# mcu_v1.net
KiCad netlist of a schematic drawn in Altium Designer
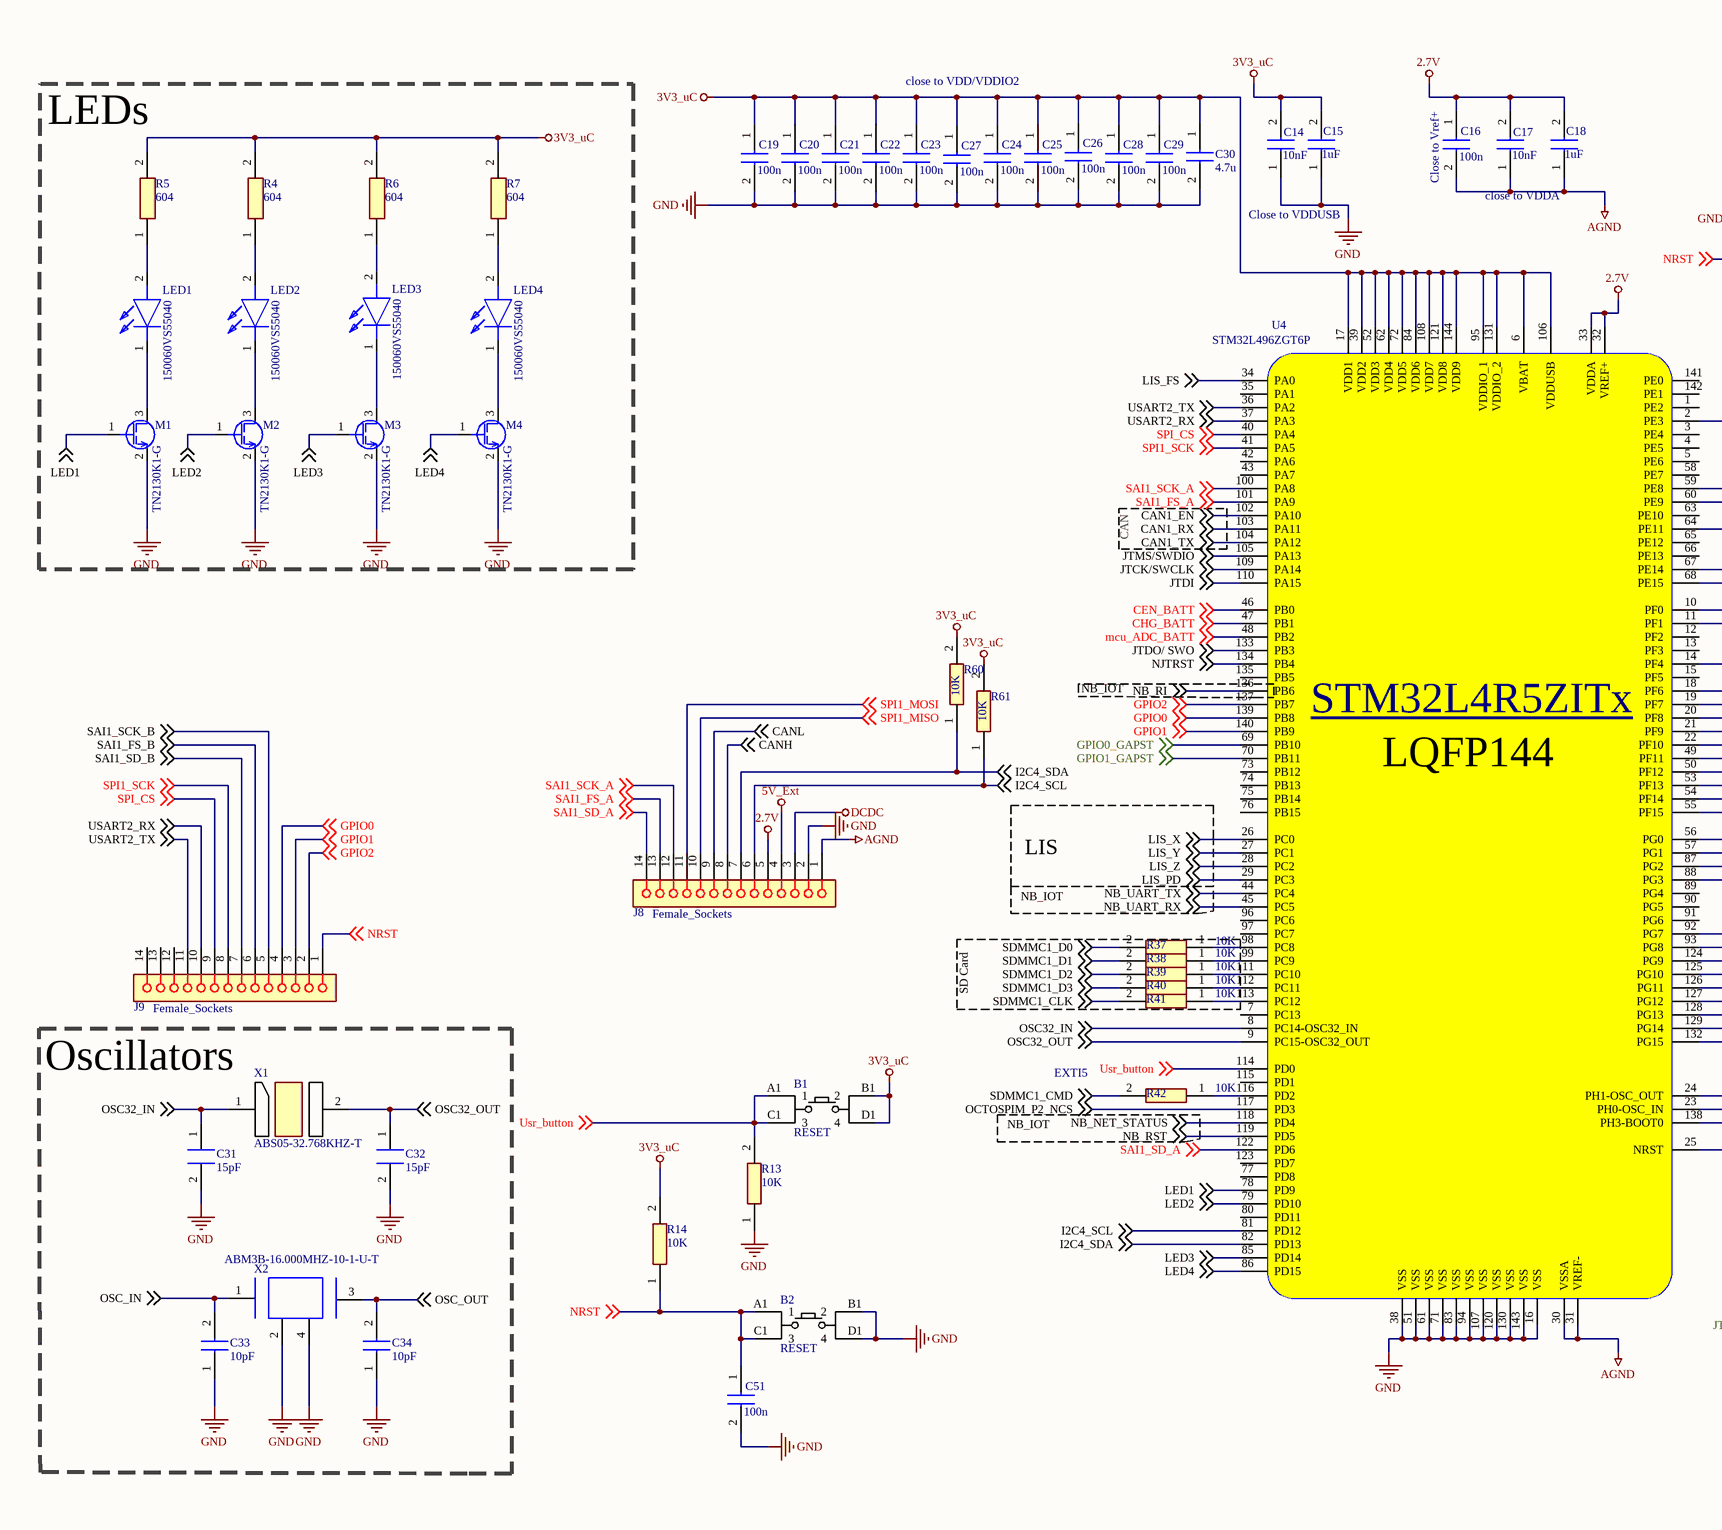
[diagram p0: mcu_v1.SchDoc, left]
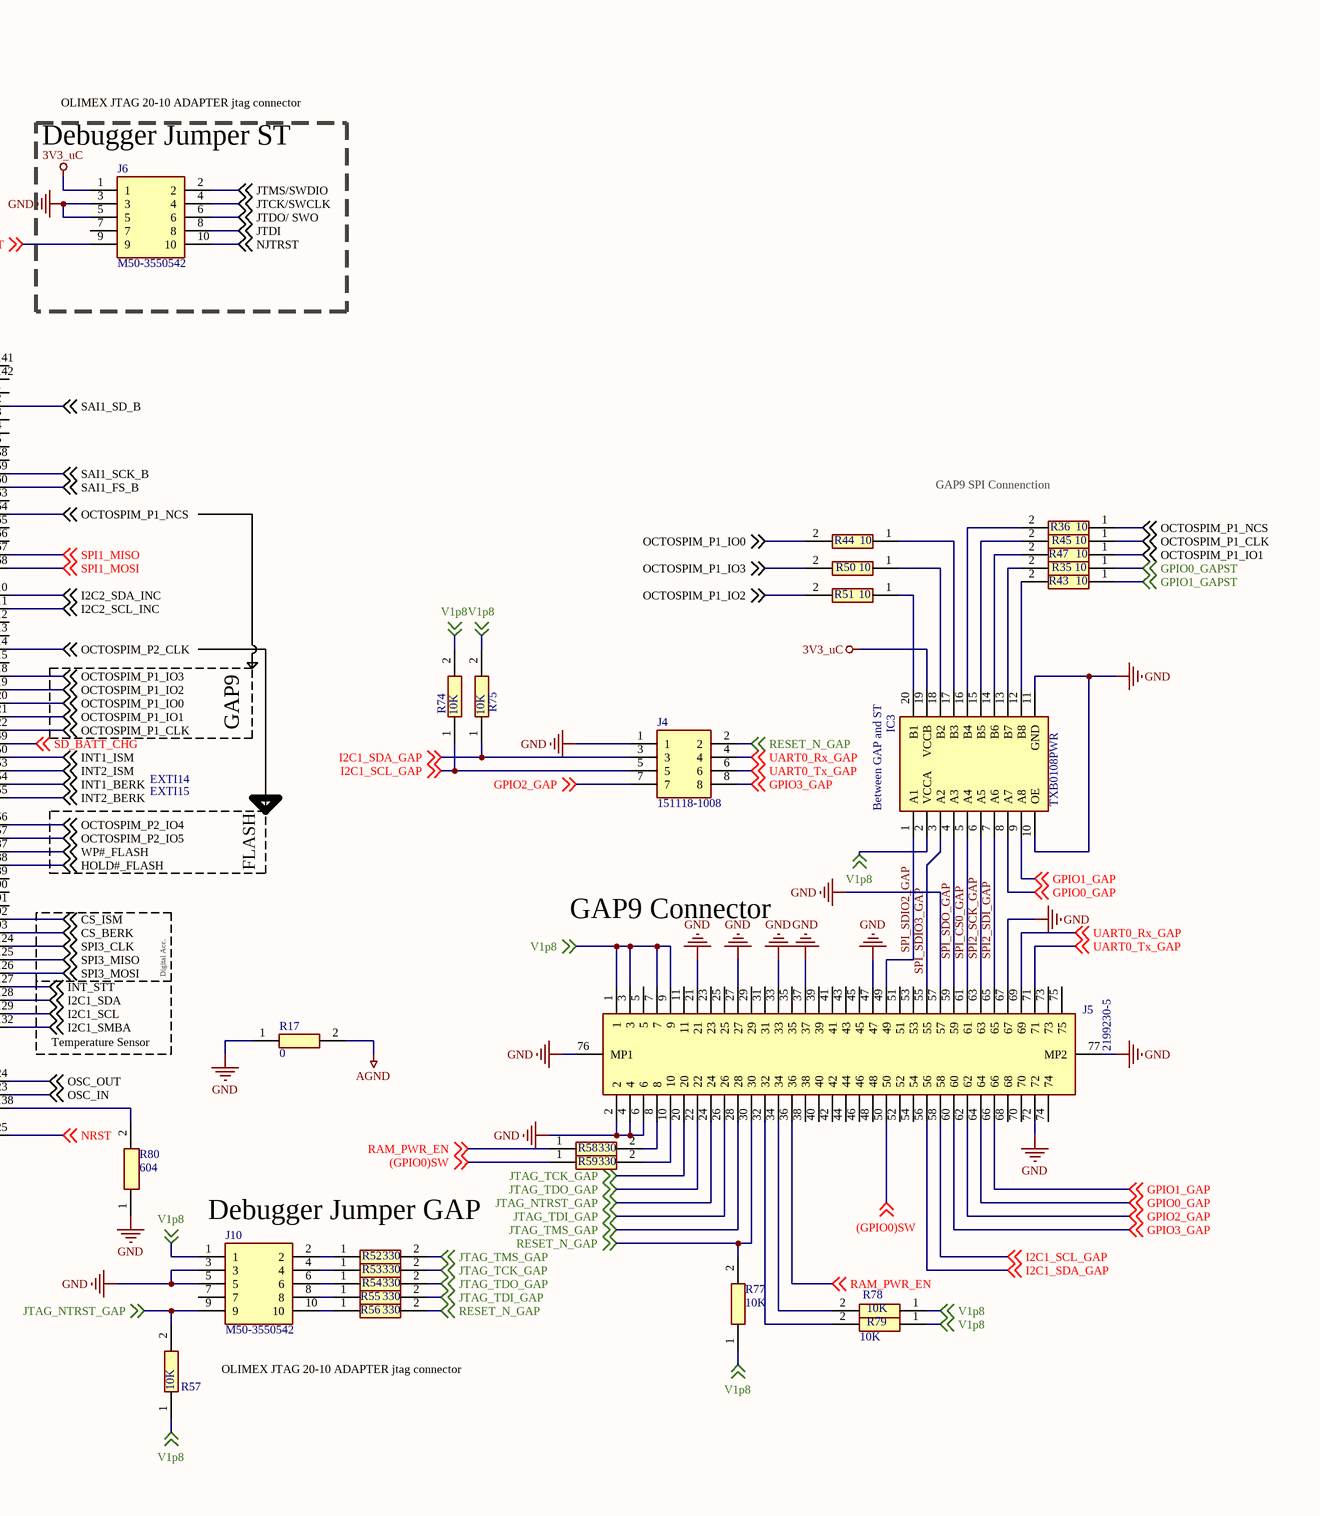
[diagram p1: mcu_v1.SchDoc, right]

(export (version "E")
  (design (tool "Eeschema 10.0.6"))
  (components
    (comp (ref "B1")
      (value "RESET")
      (footprint "PTS645SM43JSMTR92LFS")
      (description "Switch Tactile SPST N.O Round Button 12V 50mA 1.57N Solder Surface Mount T/R")
      (fields
        (field (name "MANUFACTURER") "C&K Components")
        (field (name "MANUFACTURER PART NUMBER") "PTS645SM43JSMTR92LFS")
      )
      (libsource (lib "shm_schem_lib") (part "PTS645SM43JSMTR92LFS"))
    )
    (comp (ref "B2")
      (value "RESET")
      (footprint "PTS645SM43JSMTR92LFS")
      (description "Switch Tactile SPST N.O Round Button 12V 50mA 1.57N Solder Surface Mount T/R")
      (fields
        (field (name "MANUFACTURER") "C&K Components")
        (field (name "MANUFACTURER PART NUMBER") "PTS645SM43JSMTR92LFS")
      )
      (libsource (lib "shm_schem_lib") (part "PTS645SM43JSMTR92LFS"))
    )
    (comp (ref "C14")
      (value "10nF")
      (footprint "SamacSys:CAPC1608X87N")
      (description "Capacitor")
      (fields (field (name "MANUFACTURER_PART_NUMBER") "885012206014"))
      (libsource (lib "*") (part "885012206014"))
    )
    (comp (ref "C15")
      (value "1uF")
      (footprint "SamacSys:CAPC2012X100N")
      (description "Capacitor")
      (fields (field (name "MANUFACTURER_PART_NUMBER") "C0805C105K4RACTU"))
      (libsource (lib "*") (part "C0805C105K4RACTU"))
    )
    (comp (ref "C16")
      (value "100n")
      (footprint "SamacSys:CAPC1608X87N")
      (description "Capacitor")
      (fields (field (name "MANUFACTURER_PART_NUMBER") "885012206071"))
      (libsource (lib "*") (part "885012206071"))
    )
    (comp (ref "C17")
      (value "10nF")
      (footprint "CAPC1608X87N")
      (description "Capacitor")
      (fields (field (name "MANUFACTURER_PART_NUMBER") "885012206014"))
      (libsource (lib "*") (part "885012206014"))
    )
    (comp (ref "C18")
      (value "1uF")
      (footprint "SamacSys:CAPC2012X100N")
      (description "Capacitor")
      (fields (field (name "MANUFACTURER_PART_NUMBER") "C0805C105K4RACTU"))
      (libsource (lib "*") (part "C0805C105K4RACTU"))
    )
    (comp (ref "C19")
      (value "100n")
      (footprint "SamacSys:CAPC1608X87N")
      (description "Capacitor")
      (fields (field (name "MANUFACTURER_PART_NUMBER") "885012206071"))
      (libsource (lib "*") (part "885012206071"))
    )
    (comp (ref "C20")
      (value "100n")
      (footprint "SamacSys:CAPC1608X87N")
      (description "Capacitor")
      (fields (field (name "MANUFACTURER_PART_NUMBER") "885012206071"))
      (libsource (lib "*") (part "885012206071"))
    )
    (comp (ref "C21")
      (value "100n")
      (footprint "SamacSys:CAPC1608X87N")
      (description "Capacitor")
      (fields (field (name "MANUFACTURER_PART_NUMBER") "885012206071"))
      (libsource (lib "*") (part "885012206071"))
    )
    (comp (ref "C22")
      (value "100n")
      (footprint "SamacSys:CAPC1608X87N")
      (description "Capacitor")
      (fields (field (name "MANUFACTURER_PART_NUMBER") "885012206071"))
      (libsource (lib "*") (part "885012206071"))
    )
    (comp (ref "C23")
      (value "100n")
      (footprint "SamacSys:CAPC1608X87N")
      (description "Capacitor")
      (fields (field (name "MANUFACTURER_PART_NUMBER") "885012206071"))
      (libsource (lib "*") (part "885012206071"))
    )
    (comp (ref "C24")
      (value "100n")
      (footprint "SamacSys:CAPC1608X87N")
      (description "Capacitor")
      (fields (field (name "MANUFACTURER_PART_NUMBER") "885012206071"))
      (libsource (lib "*") (part "885012206071"))
    )
    (comp (ref "C25")
      (value "100n")
      (footprint "SamacSys:CAPC1608X87N")
      (description "Capacitor")
      (fields (field (name "MANUFACTURER_PART_NUMBER") "885012206071"))
      (libsource (lib "*") (part "885012206071"))
    )
    (comp (ref "C26")
      (value "100n")
      (footprint "SamacSys:CAPC1608X87N")
      (description "Capacitor")
      (fields (field (name "MANUFACTURER_PART_NUMBER") "885012206071"))
      (libsource (lib "*") (part "885012206071"))
    )
    (comp (ref "C27")
      (value "100n")
      (footprint "SamacSys:CAPC1608X87N")
      (description "Capacitor")
      (fields (field (name "MANUFACTURER_PART_NUMBER") "885012206071"))
      (libsource (lib "*") (part "885012206071"))
    )
    (comp (ref "C28")
      (value "100n")
      (footprint "SamacSys:CAPC1608X87N")
      (description "Capacitor")
      (fields (field (name "MANUFACTURER_PART_NUMBER") "885012206071"))
      (libsource (lib "*") (part "885012206071"))
    )
    (comp (ref "C29")
      (value "100n")
      (footprint "SamacSys:CAPC1608X87N")
      (description "Capacitor")
      (fields (field (name "MANUFACTURER_PART_NUMBER") "885012206071"))
      (libsource (lib "*") (part "885012206071"))
    )
    (comp (ref "C30")
      (value "4.7u")
      (footprint "SamacSys:CAPC3216X100N")
      (description "Capacitor")
      (fields (field (name "MANUFACTURER_PART_NUMBER") "C1206C224J1RACAUTO"))
      (libsource (lib "*") (part "C1206C224J1RACAUTO"))
    )
    (comp (ref "C31")
      (value "15pF")
      (footprint "CAPC1608X87N")
      (description "CAP CER 15PF 16V C0G/NP0 0603")
      (fields
        (field (name "MANUFACTURER") "Vishay Vitramon")
        (field (name "MANUFACTURER PART NUMBER") "VJ0603A150KXJPW1BC")
      )
      (libsource (lib "shm_schem_lib") (part "VJ0603A150KXJPW1BC"))
    )
    (comp (ref "C32")
      (value "15pF")
      (footprint "CAPC1608X87N")
      (description "CAP CER 15PF 16V C0G/NP0 0603")
      (fields
        (field (name "MANUFACTURER") "Vishay Vitramon")
        (field (name "MANUFACTURER PART NUMBER") "VJ0603A150KXJPW1BC")
      )
      (libsource (lib "shm_schem_lib") (part "VJ0603A150KXJPW1BC"))
    )
    (comp (ref "C33")
      (value "10pF")
      (footprint "SamacSys:CAPC1608X87N")
      (description "Capacitor")
      (fields
        (field (name "MOUSER2 PART NUMBER") "80-C0603C100K4GACTU")
        (field (name "MANUFACTURER_PART_NUMBER") "C0603C100K4GACTU")
      )
      (libsource (lib "*") (part "C0603C100K4GACTU"))
    )
    (comp (ref "C34")
      (value "10pF")
      (footprint "SamacSys:CAPC1608X87N")
      (description "Capacitor")
      (fields
        (field (name "MOUSER2 PART NUMBER") "80-C0603C100K4GACTU")
        (field (name "MANUFACTURER_PART_NUMBER") "C0603C100K4GACTU")
      )
      (libsource (lib "*") (part "C0603C100K4GACTU"))
    )
    (comp (ref "C51")
      (value "100n")
      (footprint "SamacSys:CAPC1608X87N")
      (description "Capacitor")
      (fields (field (name "MANUFACTURER_PART_NUMBER") "885012206071"))
      (libsource (lib "*") (part "885012206071"))
    )
    (comp (ref "IC3")
      (value "TXB0108PWR")
      (footprint "SOP65P640X120-20N")
      (description "Integrated Circuit")
      (fields (field (name "MOUSER2 PART NUMBER") "595-TXB0108PWR"))
      (libsource (lib "*") (part "TXB0108PWR"))
    )
    (comp (ref "J4")
      (value "151118-1008")
      (footprint "1511181008")
      (description "Connector")
      (libsource (lib "*") (part "151118-1008"))
    )
    (comp (ref "J5")
      (value "2199230-5")
      (footprint "21992305")
      (description "Connector")
      (fields (field (name "MOUSER2 PART NUMBER") "571-2199230-5"))
      (libsource (lib "*") (part "2199230-5"))
    )
    (comp (ref "J6")
      (value "M50-3550542")
      (footprint "SamacSys:SHDR10W40P127_2X5_2083X565X1160P")
      (description "Connector")
      (libsource (lib "*") (part "M50-3550542"))
    )
    (comp (ref "J8")
      (value "Female_Sockets")
      (footprint "BCS-114-XXX-S-TE")
      (description "Conn Socket Strip SKT 14 POS 2.54mm Solder ST Top Entry Thru-Hole TIGER CLAW™ Tube")
      (fields
        (field (name "MANUFACTURER") "Samtec")
        (field (name "MANUFACTURER PART NUMBER") "BCS-114-L-S-TE")
      )
      (libsource (lib "shm_schem_lib") (part "BCS-114-L-S-TE"))
    )
    (comp (ref "J9")
      (value "Female_Sockets")
      (footprint "BCS-114-XXX-S-TE")
      (description "Conn Socket Strip SKT 14 POS 2.54mm Solder ST Top Entry Thru-Hole TIGER CLAW™ Tube")
      (fields
        (field (name "MANUFACTURER") "Samtec")
        (field (name "MANUFACTURER PART NUMBER") "BCS-114-L-S-TE")
      )
      (libsource (lib "shm_schem_lib") (part "BCS-114-L-S-TE"))
    )
    (comp (ref "J10")
      (value "M50-3550542")
      (footprint "SHDR10W40P127_2X5_2083X565X1160P")
      (description "Connector")
      (libsource (lib "*") (part "M50-3550542"))
    )
    (comp (ref "LED1")
      (value "150060VS55040")
      (footprint "SamacSys:LEDM168X50N")
      (description "LED")
      (libsource (lib "*") (part "150060VS55040"))
    )
    (comp (ref "LED2")
      (value "150060VS55040")
      (footprint "SamacSys:LEDM168X50N")
      (description "LED")
      (libsource (lib "*") (part "150060VS55040"))
    )
    (comp (ref "LED3")
      (value "150060VS55040")
      (footprint "SamacSys:LEDM168X50N")
      (description "LED")
      (libsource (lib "*") (part "150060VS55040"))
    )
    (comp (ref "LED4")
      (value "150060VS55040")
      (footprint "SamacSys:LEDM168X50N")
      (description "LED")
      (libsource (lib "*") (part "150060VS55040"))
    )
    (comp (ref "M1")
      (value "TN2130K1-G")
      (footprint "SOT95P237X112-3N")
      (description "Mosfet, N-Channel Enhancement-Mode, 300V, 25 Ohm Rohs Compliant: Yes")
      (fields (field (name "MANUFACTURER") "Microchip Supertex"))
      (libsource (lib "shm_schem_lib") (part "TN2130K1-G"))
    )
    (comp (ref "M2")
      (value "TN2130K1-G")
      (footprint "SOT95P237X112-3N")
      (description "Mosfet, N-Channel Enhancement-Mode, 300V, 25 Ohm Rohs Compliant: Yes")
      (fields (field (name "MANUFACTURER") "Microchip Supertex"))
      (libsource (lib "shm_schem_lib") (part "TN2130K1-G"))
    )
    (comp (ref "M3")
      (value "TN2130K1-G")
      (footprint "SOT95P237X112-3N")
      (description "Mosfet, N-Channel Enhancement-Mode, 300V, 25 Ohm Rohs Compliant: Yes")
      (fields (field (name "MANUFACTURER") "Microchip Supertex"))
      (libsource (lib "shm_schem_lib") (part "TN2130K1-G"))
    )
    (comp (ref "M4")
      (value "TN2130K1-G")
      (footprint "SOT95P237X112-3N")
      (description "Mosfet, N-Channel Enhancement-Mode, 300V, 25 Ohm Rohs Compliant: Yes")
      (fields (field (name "MANUFACTURER") "Microchip Supertex"))
      (libsource (lib "shm_schem_lib") (part "TN2130K1-G"))
    )
    (comp (ref "R4")
      (value "604")
      (footprint "RESC1608X55N")
      (description "Res Thin Film 0603 604 Ohm 1% 1/10W ±50ppm/°C Molded SMD SMD Paper T/R")
      (fields
        (field (name "MANUFACTURER") "Yageo")
        (field (name "MANUFACTURER PART NUMBER") "RT0603FRE07604RL")
      )
      (libsource (lib "shm_schem_lib") (part "RT0603FRE07604RL"))
    )
    (comp (ref "R5")
      (value "604")
      (footprint "RESC1608X55N")
      (description "Res Thin Film 0603 604 Ohm 1% 1/10W ±50ppm/°C Molded SMD SMD Paper T/R")
      (fields
        (field (name "MANUFACTURER") "Yageo")
        (field (name "MANUFACTURER PART NUMBER") "RT0603FRE07604RL")
      )
      (libsource (lib "shm_schem_lib") (part "RT0603FRE07604RL"))
    )
    (comp (ref "R6")
      (value "604")
      (footprint "RESC1608X55N")
      (description "Res Thin Film 0603 604 Ohm 1% 1/10W ±50ppm/°C Molded SMD SMD Paper T/R")
      (fields
        (field (name "MANUFACTURER") "Yageo")
        (field (name "MANUFACTURER PART NUMBER") "RT0603FRE07604RL")
      )
      (libsource (lib "shm_schem_lib") (part "RT0603FRE07604RL"))
    )
    (comp (ref "R7")
      (value "604")
      (footprint "RESC1608X55N")
      (description "Res Thin Film 0603 604 Ohm 1% 1/10W ±50ppm/°C Molded SMD SMD Paper T/R")
      (fields
        (field (name "MANUFACTURER") "Yageo")
        (field (name "MANUFACTURER PART NUMBER") "RT0603FRE07604RL")
      )
      (libsource (lib "shm_schem_lib") (part "RT0603FRE07604RL"))
    )
    (comp (ref "R13")
      (value "10K")
      (footprint "ERJ3EK_(0603)")
      (description "Resistor")
      (fields
        (field (name "MOUSER2 PART NUMBER") "667-ERJ-3EKF1002V")
        (field (name "MANUFACTURER_PART_NUMBER") "ERJ-3EKF1002V")
      )
      (libsource (lib "*") (part "ERJ-3EKF1002V"))
    )
    (comp (ref "R14")
      (value "10K")
      (footprint "RESC1608X55N")
      (description "Resistor")
      (fields
        (field (name "MOUSER2 PART NUMBER") "667-ERJ-3EKF1002V")
        (field (name "MANUFACTURER_PART_NUMBER") "ERJ-3EKF1002V")
      )
      (libsource (lib "*") (part "ERJ-3EKF1002V"))
    )
    (comp (ref "R17")
      (value "0")
      (footprint "SamacSys:RESC1608X55N")
      (description "Resistor")
      (fields (field (name "MANUFACTURER_PART_NUMBER") "RC0603FR-070RL"))
      (libsource (lib "*") (part "RC0603FR-070RL"))
    )
    (comp (ref "R35")
      (value "10")
      (footprint "SamacSys:RESC1005X40N")
      (description "Resistor")
      (fields (field (name "MANUFACTURER_PART_NUMBER") "CR0402-FX-10R0GLF"))
      (libsource (lib "*") (part "CR0402-FX-10R0GLF"))
    )
    (comp (ref "R36")
      (value "10")
      (footprint "SamacSys:RESC1005X40N")
      (description "Resistor")
      (fields (field (name "MANUFACTURER_PART_NUMBER") "CR0402-FX-10R0GLF"))
      (libsource (lib "*") (part "CR0402-FX-10R0GLF"))
    )
    (comp (ref "R37")
      (value "10K")
      (footprint "SamacSys:ERJ3EK_(0603)")
      (description "Resistor")
      (fields
        (field (name "MOUSER2 PART NUMBER") "667-ERJ-3EKF1002V")
        (field (name "MANUFACTURER_PART_NUMBER") "ERJ-3EKF1002V")
      )
      (libsource (lib "") (part "ERJ-3EKF1002V_1"))
    )
    (comp (ref "R38")
      (value "10K")
      (footprint "SamacSys:ERJ3EK_(0603)")
      (description "Resistor")
      (fields
        (field (name "MOUSER2 PART NUMBER") "667-ERJ-3EKF1002V")
        (field (name "MANUFACTURER_PART_NUMBER") "ERJ-3EKF1002V")
      )
      (libsource (lib "") (part "ERJ-3EKF1002V_1"))
    )
    (comp (ref "R39")
      (value "10K")
      (footprint "SamacSys:ERJ3EK_(0603)")
      (description "Resistor")
      (fields
        (field (name "MOUSER2 PART NUMBER") "667-ERJ-3EKF1002V")
        (field (name "MANUFACTURER_PART_NUMBER") "ERJ-3EKF1002V")
      )
      (libsource (lib "") (part "ERJ-3EKF1002V_1"))
    )
    (comp (ref "R40")
      (value "10K")
      (footprint "SamacSys:ERJ3EK_(0603)")
      (description "Resistor")
      (fields
        (field (name "MOUSER2 PART NUMBER") "667-ERJ-3EKF1002V")
        (field (name "MANUFACTURER_PART_NUMBER") "ERJ-3EKF1002V")
      )
      (libsource (lib "") (part "ERJ-3EKF1002V_1"))
    )
    (comp (ref "R41")
      (value "10K")
      (footprint "SamacSys:ERJ3EK_(0603)")
      (description "Resistor")
      (fields
        (field (name "MOUSER2 PART NUMBER") "667-ERJ-3EKF1002V")
        (field (name "MANUFACTURER_PART_NUMBER") "ERJ-3EKF1002V")
      )
      (libsource (lib "") (part "ERJ-3EKF1002V_1"))
    )
    (comp (ref "R42")
      (value "10K")
      (footprint "SamacSys:ERJ3EK_(0603)")
      (description "Resistor")
      (fields
        (field (name "MOUSER2 PART NUMBER") "667-ERJ-3EKF1002V")
        (field (name "MANUFACTURER_PART_NUMBER") "ERJ-3EKF1002V")
      )
      (libsource (lib "") (part "ERJ-3EKF1002V_1"))
    )
    (comp (ref "R43")
      (value "10")
      (footprint "SamacSys:RESC1005X40N")
      (description "Resistor")
      (fields (field (name "MANUFACTURER_PART_NUMBER") "CR0402-FX-10R0GLF"))
      (libsource (lib "*") (part "CR0402-FX-10R0GLF"))
    )
    (comp (ref "R44")
      (value "10")
      (footprint "SamacSys:RESC1005X40N")
      (description "Resistor")
      (fields (field (name "MANUFACTURER_PART_NUMBER") "CR0402-FX-10R0GLF"))
      (libsource (lib "*") (part "CR0402-FX-10R0GLF"))
    )
    (comp (ref "R45")
      (value "10")
      (footprint "SamacSys:RESC1005X40N")
      (description "Resistor")
      (fields (field (name "MANUFACTURER_PART_NUMBER") "CR0402-FX-10R0GLF"))
      (libsource (lib "*") (part "CR0402-FX-10R0GLF"))
    )
    (comp (ref "R47")
      (value "10")
      (footprint "SamacSys:RESC1005X40N")
      (description "Resistor")
      (fields (field (name "MANUFACTURER_PART_NUMBER") "CR0402-FX-10R0GLF"))
      (libsource (lib "*") (part "CR0402-FX-10R0GLF"))
    )
    (comp (ref "R50")
      (value "10")
      (footprint "SamacSys:RESC1005X40N")
      (description "Resistor")
      (fields (field (name "MANUFACTURER_PART_NUMBER") "CR0402-FX-10R0GLF"))
      (libsource (lib "*") (part "CR0402-FX-10R0GLF"))
    )
    (comp (ref "R51")
      (value "10")
      (footprint "SamacSys:RESC1005X40N")
      (description "Resistor")
      (fields (field (name "MANUFACTURER_PART_NUMBER") "CR0402-FX-10R0GLF"))
      (libsource (lib "*") (part "CR0402-FX-10R0GLF"))
    )
    (comp (ref "R52")
      (value "330")
      (footprint "RESC3216X51N")
      (description "Resistor")
      (fields (field (name "MANUFACTURER_PART_NUMBER") "PHPA1206E3300BST1"))
      (libsource (lib "*") (part "PHPA1206E3300BST1"))
    )
    (comp (ref "R53")
      (value "330")
      (footprint "RESC3216X51N")
      (description "Resistor")
      (fields (field (name "MANUFACTURER_PART_NUMBER") "PHPA1206E3300BST1"))
      (libsource (lib "*") (part "PHPA1206E3300BST1"))
    )
    (comp (ref "R54")
      (value "330")
      (footprint "RESC3216X51N")
      (description "Resistor")
      (fields (field (name "MANUFACTURER_PART_NUMBER") "PHPA1206E3300BST1"))
      (libsource (lib "*") (part "PHPA1206E3300BST1"))
    )
    (comp (ref "R55")
      (value "330")
      (footprint "RESC3216X51N")
      (description "Resistor")
      (fields (field (name "MANUFACTURER_PART_NUMBER") "PHPA1206E3300BST1"))
      (libsource (lib "*") (part "PHPA1206E3300BST1"))
    )
    (comp (ref "R56")
      (value "330")
      (footprint "RESC3216X51N")
      (description "Resistor")
      (fields (field (name "MANUFACTURER_PART_NUMBER") "PHPA1206E3300BST1"))
      (libsource (lib "*") (part "PHPA1206E3300BST1"))
    )
    (comp (ref "R57")
      (value "10K")
      (footprint "ERJ3EK_(0603)")
      (description "Resistor")
      (fields
        (field (name "MOUSER2 PART NUMBER") "667-ERJ-3EKF1002V")
        (field (name "MANUFACTURER_PART_NUMBER") "ERJ-3EKF1002V")
      )
      (libsource (lib "*") (part "ERJ-3EKF1002V"))
    )
    (comp (ref "R58")
      (value "330")
      (footprint "RESC3216X51N")
      (description "Resistor")
      (fields (field (name "MANUFACTURER_PART_NUMBER") "PHPA1206E3300BST1"))
      (libsource (lib "*") (part "PHPA1206E3300BST1"))
    )
    (comp (ref "R59")
      (value "330")
      (footprint "RESC3216X51N")
      (description "Resistor")
      (fields (field (name "MANUFACTURER_PART_NUMBER") "PHPA1206E3300BST1"))
      (libsource (lib "*") (part "PHPA1206E3300BST1"))
    )
    (comp (ref "R60")
      (value "10K")
      (footprint "SamacSys:ERJP14_(1210)")
      (description "Resistor")
      (fields (field (name "MANUFACTURER_PART_NUMBER") "ERJ-P14J103U"))
      (libsource (lib "*") (part "ERJ-P14J103U"))
    )
    (comp (ref "R61")
      (value "10K")
      (footprint "SamacSys:ERJP14_(1210)")
      (description "Resistor")
      (fields (field (name "MANUFACTURER_PART_NUMBER") "ERJ-P14J103U"))
      (libsource (lib "*") (part "ERJ-P14J103U"))
    )
    (comp (ref "R74")
      (value "10K")
      (footprint "ERJ3EK_(0603)")
      (description "Resistor")
      (fields
        (field (name "MOUSER2 PART NUMBER") "667-ERJ-3EKF1002V")
        (field (name "MANUFACTURER_PART_NUMBER") "ERJ-3EKF1002V")
      )
      (libsource (lib "*") (part "ERJ-3EKF1002V"))
    )
    (comp (ref "R75")
      (value "10K")
      (footprint "ERJ3EK_(0603)")
      (description "Resistor")
      (fields
        (field (name "MOUSER2 PART NUMBER") "667-ERJ-3EKF1002V")
        (field (name "MANUFACTURER_PART_NUMBER") "ERJ-3EKF1002V")
      )
      (libsource (lib "*") (part "ERJ-3EKF1002V"))
    )
    (comp (ref "R77")
      (value "10K")
      (footprint "SamacSys:ERJP14_(1210)")
      (description "Resistor")
      (fields (field (name "MANUFACTURER_PART_NUMBER") "ERJ-P14J103U"))
      (libsource (lib "*") (part "ERJ-P14J103U"))
    )
    (comp (ref "R78")
      (value "10K")
      (footprint "ERJ3EK_(0603)")
      (description "Resistor")
      (fields
        (field (name "MOUSER2 PART NUMBER") "667-ERJ-3EKF1002V")
        (field (name "MANUFACTURER_PART_NUMBER") "ERJ-3EKF1002V")
      )
      (libsource (lib "") (part "ERJ-3EKF1002V_1"))
    )
    (comp (ref "R79")
      (value "10K")
      (footprint "ERJ3EK_(0603)")
      (description "Resistor")
      (fields
        (field (name "MOUSER2 PART NUMBER") "667-ERJ-3EKF1002V")
        (field (name "MANUFACTURER_PART_NUMBER") "ERJ-3EKF1002V")
      )
      (libsource (lib "") (part "ERJ-3EKF1002V_1"))
    )
    (comp (ref "R80")
      (value "604")
      (footprint "RESC1608X55N")
      (description "Res Thin Film 0603 604 Ohm 1% 1/10W ±50ppm/°C Molded SMD SMD Paper T/R")
      (fields
        (field (name "MANUFACTURER") "Yageo")
        (field (name "MANUFACTURER PART NUMBER") "RT0603FRE07604RL")
      )
      (libsource (lib "shm_schem_lib") (part "RT0603FRE07604RL"))
    )
    (comp (ref "U4")
      (value "STM32L496ZGT6P")
      (footprint "QFP50P2200X2200X160-144N")
      (description "Ultra-low-power with FPU ARM Cortex-M4 MCU 80 MHz with 1 Mbyte Flash, USB OTG, LCD, DFSDM")
      (fields (field (name "MANUFACTURER") "STMicroelectronics"))
      (libsource (lib "shm_schem_lib") (part "STM32L496ZGT6P"))
    )
    (comp (ref "X1")
      (value "ABS05-32.768KHZ-T")
      (footprint "ABS0532768KHZT")
      (description "ABRACON - ABS05-32.768KHZ-T - Crystal, 32.768 kHz, SMD, 1.6mm x 1mm, 12.5 pF, 20 ppm, ABS05 Series")
      (fields (field (name "MANUFACTURER") "Abracon") (field (name "TOLERANCE") "20ppm"))
      (libsource (lib "shm_schem_lib") (part "ABS05-32.768KHZ-T"))
    )
    (comp (ref "X2")
      (value "ABM3B-16.000MHZ-10-1-U-T")
      (footprint "OSCCC500X320X110-4N")
      (description "Crystal, Ceramic, 16.000Mhz, 10Pf, 10Ppm-10+60C, 5 X 3.2 X 1 Rohs Compliant: Yes")
      (fields (field (name "MANUFACTURER") "Abracon") (field (name "TOLERANCE") "10ppm"))
      (libsource (lib "shm_schem_lib") (part "ABM3B-16.000MHZ-10-1-U-T"))
    )
  )
  (nets
    (net (code "1") (name "(GPIO0)SW") (class "Default")
      (node (ref "J5") (pin "50") (pinfunction "50_50") (pintype "passive"))
      (node (ref "R59") (pin "1") (pinfunction "1_1") (pintype "passive"))
    )
    (net (code "2") (name "/SPI2_SCK_GAP") (class "Default")
      (node (ref "IC3") (pin "6") (pinfunction "A5_6") (pintype "passive"))
      (node (ref "J5") (pin "63") (pinfunction "63_63") (pintype "passive"))
    )
    (net (code "3") (name "/SPI2_SDI_GAP") (class "Default")
      (node (ref "IC3") (pin "7") (pinfunction "A6_7") (pintype "passive"))
      (node (ref "J5") (pin "65") (pinfunction "65_65") (pintype "passive"))
    )
    (net (code "4") (name "/SPI_CS0_GAP") (class "Default")
      (node (ref "IC3") (pin "5") (pinfunction "A4_5") (pintype "passive"))
      (node (ref "J5") (pin "61") (pinfunction "61_61") (pintype "passive"))
    )
    (net (code "5") (name "/SPI_SDIO2_GAP") (class "Default")
      (node (ref "IC3") (pin "1") (pinfunction "A1_1") (pintype "passive"))
      (node (ref "J5") (pin "49") (pinfunction "49_49") (pintype "passive"))
    )
    (net (code "6") (name "/SPI_SDIO3_GAP") (class "Default")
      (node (ref "IC3") (pin "3") (pinfunction "A2_3") (pintype "passive"))
      (node (ref "J5") (pin "55") (pinfunction "55_55") (pintype "passive"))
    )
    (net (code "7") (name "/SPI_SDO_GAP") (class "Default")
      (node (ref "IC3") (pin "4") (pinfunction "A3_4") (pintype "passive"))
      (node (ref "J5") (pin "59") (pinfunction "59_59") (pintype "passive"))
    )
    (net (code "8") (name "2.7V") (class "Default")
      (node (ref "C16") (pin "1") (pinfunction "1_1") (pintype "passive"))
      (node (ref "C17") (pin "2") (pinfunction "2_2") (pintype "passive"))
      (node (ref "C18") (pin "2") (pinfunction "2_2") (pintype "passive"))
      (node (ref "J8") (pin "5") (pinfunction "5_5") (pintype "passive"))
      (node (ref "U4") (pin "32") (pinfunction "VREF+_32") (pintype "passive"))
      (node (ref "U4") (pin "33") (pinfunction "VDDA_33") (pintype "passive"))
    )
    (net (code "9") (name "3V3_uC") (class "Default")
      (node (ref "B1") (pin "B1") (pinfunction "2_B1") (pintype "passive"))
      (node (ref "B1") (pin "D1") (pinfunction "4_D1") (pintype "passive"))
      (node (ref "C14") (pin "2") (pinfunction "2_2") (pintype "passive"))
      (node (ref "C15") (pin "2") (pinfunction "2_2") (pintype "passive"))
      (node (ref "C19") (pin "1") (pinfunction "1_1") (pintype "passive"))
      (node (ref "C20") (pin "1") (pinfunction "1_1") (pintype "passive"))
      (node (ref "C21") (pin "1") (pinfunction "1_1") (pintype "passive"))
      (node (ref "C22") (pin "1") (pinfunction "1_1") (pintype "passive"))
      (node (ref "C23") (pin "1") (pinfunction "1_1") (pintype "passive"))
      (node (ref "C24") (pin "1") (pinfunction "1_1") (pintype "passive"))
      (node (ref "C25") (pin "1") (pinfunction "1_1") (pintype "passive"))
      (node (ref "C26") (pin "1") (pinfunction "1_1") (pintype "passive"))
      (node (ref "C27") (pin "1") (pinfunction "1_1") (pintype "passive"))
      (node (ref "C28") (pin "1") (pinfunction "1_1") (pintype "passive"))
      (node (ref "C29") (pin "1") (pinfunction "1_1") (pintype "passive"))
      (node (ref "C30") (pin "1") (pinfunction "1_1") (pintype "passive"))
      (node (ref "IC3") (pin "19") (pinfunction "VCCB_19") (pintype "passive"))
      (node (ref "J6") (pin "1") (pinfunction "1_1") (pintype "passive"))
      (node (ref "R14") (pin "2") (pinfunction "2_2") (pintype "passive"))
      (node (ref "R4") (pin "2") (pinfunction "2_2") (pintype "passive"))
      (node (ref "R5") (pin "2") (pinfunction "2_2") (pintype "passive"))
      (node (ref "R6") (pin "2") (pinfunction "2_2") (pintype "passive"))
      (node (ref "R60") (pin "2") (pinfunction "2_2") (pintype "passive"))
      (node (ref "R61") (pin "2") (pinfunction "2_2") (pintype "passive"))
      (node (ref "R7") (pin "2") (pinfunction "2_2") (pintype "passive"))
      (node (ref "U4") (pin "106") (pinfunction "VDDUSB_106") (pintype "passive"))
      (node (ref "U4") (pin "108") (pinfunction "VDD7_108") (pintype "passive"))
      (node (ref "U4") (pin "121") (pinfunction "VDD8_121") (pintype "passive"))
      (node (ref "U4") (pin "131") (pinfunction "VDDIO_2_131") (pintype "passive"))
      (node (ref "U4") (pin "144") (pinfunction "VDD9_144") (pintype "passive"))
      (node (ref "U4") (pin "17") (pinfunction "VDD1_17") (pintype "passive"))
      (node (ref "U4") (pin "39") (pinfunction "VDD2_39") (pintype "passive"))
      (node (ref "U4") (pin "52") (pinfunction "VDD3_52") (pintype "passive"))
      (node (ref "U4") (pin "6") (pinfunction "VBAT_6") (pintype "passive"))
      (node (ref "U4") (pin "62") (pinfunction "VDD4_62") (pintype "passive"))
      (node (ref "U4") (pin "72") (pinfunction "VDD5_72") (pintype "passive"))
      (node (ref "U4") (pin "84") (pinfunction "VDD6_84") (pintype "passive"))
      (node (ref "U4") (pin "95") (pinfunction "VDDIO_1_95") (pintype "passive"))
    )
    (net (code "10") (name "5V_Ext") (class "Default")
      (node (ref "J8") (pin "4") (pinfunction "4_4") (pintype "passive"))
    )
    (net (code "11") (name "AGND") (class "Default")
      (node (ref "C16") (pin "2") (pinfunction "2_2") (pintype "passive"))
      (node (ref "C17") (pin "1") (pinfunction "1_1") (pintype "passive"))
      (node (ref "C18") (pin "1") (pinfunction "1_1") (pintype "passive"))
      (node (ref "J8") (pin "1") (pinfunction "1_1") (pintype "passive"))
      (node (ref "R17") (pin "2") (pinfunction "2_2") (pintype "passive"))
      (node (ref "U4") (pin "30") (pinfunction "VSSA_30") (pintype "passive"))
      (node (ref "U4") (pin "31") (pinfunction "VREF-_31") (pintype "passive"))
    )
    (net (code "12") (name "CAN1_EN") (class "Default")
      (node (ref "U4") (pin "102") (pinfunction "PA10_102") (pintype "passive"))
    )
    (net (code "13") (name "CAN1_RX") (class "Default")
      (node (ref "U4") (pin "103") (pinfunction "PA11_103") (pintype "passive"))
    )
    (net (code "14") (name "CAN1_TX") (class "Default")
      (node (ref "U4") (pin "104") (pinfunction "PA12_104") (pintype "passive"))
    )
    (net (code "15") (name "CANH") (class "Default")
      (node (ref "J8") (pin "8") (pinfunction "8_8") (pintype "passive"))
    )
    (net (code "16") (name "CANL") (class "Default")
      (node (ref "J8") (pin "9") (pinfunction "9_9") (pintype "passive"))
    )
    (net (code "17") (name "CEN_BATT") (class "Default")
      (node (ref "U4") (pin "46") (pinfunction "PB0_46") (pintype "passive"))
    )
    (net (code "18") (name "CHG_BATT") (class "Default")
      (node (ref "U4") (pin "47") (pinfunction "PB1_47") (pintype "passive"))
    )
    (net (code "19") (name "CS_BERK") (class "Default")
      (node (ref "U4") (pin "93") (pinfunction "PG8_93") (pintype "passive"))
    )
    (net (code "20") (name "CS_ISM") (class "Default")
      (node (ref "U4") (pin "92") (pinfunction "PG7_92") (pintype "passive"))
    )
    (net (code "21") (name "DCDC") (class "Default")
      (node (ref "J8") (pin "3") (pinfunction "3_3") (pintype "passive"))
    )
    (net (code "22") (name "GND") (class "Default")
      (node (ref "B2") (pin "B1") (pinfunction "2_B1") (pintype "passive"))
      (node (ref "B2") (pin "D1") (pinfunction "4_D1") (pintype "passive"))
      (node (ref "C14") (pin "1") (pinfunction "1_1") (pintype "passive"))
      (node (ref "C15") (pin "1") (pinfunction "1_1") (pintype "passive"))
      (node (ref "C19") (pin "2") (pinfunction "2_2") (pintype "passive"))
      (node (ref "C20") (pin "2") (pinfunction "2_2") (pintype "passive"))
      (node (ref "C21") (pin "2") (pinfunction "2_2") (pintype "passive"))
      (node (ref "C22") (pin "2") (pinfunction "2_2") (pintype "passive"))
      (node (ref "C23") (pin "2") (pinfunction "2_2") (pintype "passive"))
      (node (ref "C24") (pin "2") (pinfunction "2_2") (pintype "passive"))
      (node (ref "C25") (pin "2") (pinfunction "2_2") (pintype "passive"))
      (node (ref "C26") (pin "2") (pinfunction "2_2") (pintype "passive"))
      (node (ref "C27") (pin "2") (pinfunction "2_2") (pintype "passive"))
      (node (ref "C28") (pin "2") (pinfunction "2_2") (pintype "passive"))
      (node (ref "C29") (pin "2") (pinfunction "2_2") (pintype "passive"))
      (node (ref "C30") (pin "2") (pinfunction "2_2") (pintype "passive"))
      (node (ref "C31") (pin "2") (pinfunction "2_2") (pintype "passive"))
      (node (ref "C32") (pin "2") (pinfunction "2_2") (pintype "passive"))
      (node (ref "C33") (pin "1") (pinfunction "1_1") (pintype "passive"))
      (node (ref "C34") (pin "1") (pinfunction "1_1") (pintype "passive"))
      (node (ref "C51") (pin "2") (pinfunction "2_2") (pintype "passive"))
      (node (ref "IC3") (pin "10") (pinfunction "OE_10") (pintype "passive"))
      (node (ref "IC3") (pin "11") (pinfunction "GND_11") (pintype "passive"))
      (node (ref "J10") (pin "3") (pinfunction "3_3") (pintype "passive"))
      (node (ref "J10") (pin "5") (pinfunction "5_5") (pintype "passive"))
      (node (ref "J4") (pin "1") (pinfunction "1_1") (pintype "passive"))
      (node (ref "J5") (pin "2") (pinfunction "2_2") (pintype "passive"))
      (node (ref "J5") (pin "21") (pinfunction "21_21") (pintype "passive"))
      (node (ref "J5") (pin "27") (pinfunction "27_27") (pintype "passive"))
      (node (ref "J5") (pin "33") (pinfunction "33_33") (pintype "passive"))
      (node (ref "J5") (pin "37") (pinfunction "37_37") (pintype "passive"))
      (node (ref "J5") (pin "4") (pinfunction "4_4") (pintype "passive"))
      (node (ref "J5") (pin "47") (pinfunction "47_47") (pintype "passive"))
      (node (ref "J5") (pin "57") (pinfunction "57_57") (pintype "passive"))
      (node (ref "J5") (pin "6") (pinfunction "6_6") (pintype "passive"))
      (node (ref "J5") (pin "67") (pinfunction "67_67") (pintype "passive"))
      (node (ref "J5") (pin "72") (pinfunction "72_72") (pintype "passive"))
      (node (ref "J5") (pin "76") (pinfunction "MP1_76") (pintype "passive"))
      (node (ref "J5") (pin "77") (pinfunction "MP2_77") (pintype "passive"))
      (node (ref "J6") (pin "3") (pinfunction "3_3") (pintype "passive"))
      (node (ref "J6") (pin "5") (pinfunction "5_5") (pintype "passive"))
      (node (ref "J8") (pin "2") (pinfunction "2_2") (pintype "passive"))
      (node (ref "M1") (pin "2") (pinfunction "S_2") (pintype "passive"))
      (node (ref "M2") (pin "2") (pinfunction "S_2") (pintype "passive"))
      (node (ref "M3") (pin "2") (pinfunction "S_2") (pintype "passive"))
      (node (ref "M4") (pin "2") (pinfunction "S_2") (pintype "passive"))
      (node (ref "R13") (pin "1") (pinfunction "1_1") (pintype "passive"))
      (node (ref "R17") (pin "1") (pinfunction "1_1") (pintype "passive"))
      (node (ref "R80") (pin "1") (pinfunction "1_1") (pintype "passive"))
      (node (ref "U4") (pin "107") (pinfunction "VSS_107") (pintype "passive"))
      (node (ref "U4") (pin "120") (pinfunction "VSS_120") (pintype "passive"))
      (node (ref "U4") (pin "130") (pinfunction "VSS_130") (pintype "passive"))
      (node (ref "U4") (pin "143") (pinfunction "VSS_143") (pintype "passive"))
      (node (ref "U4") (pin "16") (pinfunction "VSS_16") (pintype "passive"))
      (node (ref "U4") (pin "38") (pinfunction "VSS_38") (pintype "passive"))
      (node (ref "U4") (pin "51") (pinfunction "VSS_51") (pintype "passive"))
      (node (ref "U4") (pin "61") (pinfunction "VSS_61") (pintype "passive"))
      (node (ref "U4") (pin "71") (pinfunction "VSS_71") (pintype "passive"))
      (node (ref "U4") (pin "83") (pinfunction "VSS_83") (pintype "passive"))
      (node (ref "U4") (pin "94") (pinfunction "VSS_94") (pintype "passive"))
      (node (ref "X2") (pin "2") (pinfunction "2_2") (pintype "passive"))
      (node (ref "X2") (pin "4") (pinfunction "4_4") (pintype "passive"))
    )
    (net (code "23") (name "GPIO0") (class "Default")
      (node (ref "J9") (pin "4") (pinfunction "4_4") (pintype "passive"))
      (node (ref "U4") (pin "139") (pinfunction "PB8_139") (pintype "passive"))
    )
    (net (code "24") (name "GPIO0_GAP") (class "Default")
      (node (ref "IC3") (pin "8") (pinfunction "A7_8") (pintype "passive"))
      (node (ref "J5") (pin "64") (pinfunction "64_64") (pintype "passive"))
    )
    (net (code "25") (name "GPIO0_GAPST") (class "Default")
      (node (ref "R35") (pin "1") (pinfunction "1_1") (pintype "passive"))
      (node (ref "U4") (pin "69") (pinfunction "PB10_69") (pintype "passive"))
    )
    (net (code "26") (name "GPIO1") (class "Default")
      (node (ref "J9") (pin "3") (pinfunction "3_3") (pintype "passive"))
      (node (ref "U4") (pin "140") (pinfunction "PB9_140") (pintype "passive"))
    )
    (net (code "27") (name "GPIO1_GAP") (class "Default")
      (node (ref "IC3") (pin "9") (pinfunction "A8_9") (pintype "passive"))
      (node (ref "J5") (pin "66") (pinfunction "66_66") (pintype "passive"))
    )
    (net (code "28") (name "GPIO1_GAPST") (class "Default")
      (node (ref "R43") (pin "1") (pinfunction "1_1") (pintype "passive"))
      (node (ref "U4") (pin "70") (pinfunction "PB11_70") (pintype "passive"))
    )
    (net (code "29") (name "GPIO2") (class "Default")
      (node (ref "J9") (pin "2") (pinfunction "2_2") (pintype "passive"))
      (node (ref "U4") (pin "137") (pinfunction "PB7_137") (pintype "passive"))
    )
    (net (code "30") (name "GPIO2_GAP") (class "Default")
      (node (ref "J4") (pin "7") (pinfunction "7_7") (pintype "passive"))
      (node (ref "J5") (pin "62") (pinfunction "62_62") (pintype "passive"))
    )
    (net (code "31") (name "GPIO3_GAP") (class "Default")
      (node (ref "J4") (pin "8") (pinfunction "8_8") (pintype "passive"))
      (node (ref "J5") (pin "60") (pinfunction "60_60") (pintype "passive"))
    )
    (net (code "32") (name "HOLD#_FLASH") (class "Default")
      (node (ref "U4") (pin "88") (pinfunction "PG3_88") (pintype "passive"))
    )
    (net (code "33") (name "I2C1_SCL") (class "Default")
      (node (ref "U4") (pin "129") (pinfunction "PG14_129") (pintype "passive"))
    )
    (net (code "34") (name "I2C1_SCL_GAP") (class "Default")
      (node (ref "J4") (pin "5") (pinfunction "5_5") (pintype "passive"))
      (node (ref "J5") (pin "58") (pinfunction "58_58") (pintype "passive"))
      (node (ref "R74") (pin "1") (pinfunction "1_1") (pintype "passive"))
    )
    (net (code "35") (name "I2C1_SDA") (class "Default")
      (node (ref "U4") (pin "128") (pinfunction "PG13_128") (pintype "passive"))
    )
    (net (code "36") (name "I2C1_SDA_GAP") (class "Default")
      (node (ref "J4") (pin "3") (pinfunction "3_3") (pintype "passive"))
      (node (ref "J5") (pin "56") (pinfunction "56_56") (pintype "passive"))
      (node (ref "R75") (pin "1") (pinfunction "1_1") (pintype "passive"))
    )
    (net (code "37") (name "I2C1_SMBA") (class "Default")
      (node (ref "U4") (pin "132") (pinfunction "PG15_132") (pintype "passive"))
    )
    (net (code "38") (name "I2C2_SCL_INC") (class "Default")
      (node (ref "U4") (pin "11") (pinfunction "PF1_11") (pintype "passive"))
    )
    (net (code "39") (name "I2C2_SDA_INC") (class "Default")
      (node (ref "U4") (pin "10") (pinfunction "PF0_10") (pintype "passive"))
    )
    (net (code "40") (name "I2C4_SCL") (class "Default")
      (node (ref "J8") (pin "6") (pinfunction "6_6") (pintype "passive"))
      (node (ref "R61") (pin "1") (pinfunction "1_1") (pintype "passive"))
      (node (ref "U4") (pin "81") (pinfunction "PD12_81") (pintype "passive"))
    )
    (net (code "41") (name "I2C4_SDA") (class "Default")
      (node (ref "J8") (pin "7") (pinfunction "7_7") (pintype "passive"))
      (node (ref "R60") (pin "1") (pinfunction "1_1") (pintype "passive"))
      (node (ref "U4") (pin "82") (pinfunction "PD13_82") (pintype "passive"))
    )
    (net (code "42") (name "INT1_BERK") (class "Default")
      (node (ref "U4") (pin "54") (pinfunction "PF14_54") (pintype "passive"))
    )
    (net (code "43") (name "INT1_ISM") (class "Default")
      (node (ref "U4") (pin "50") (pinfunction "PF12_50") (pintype "passive"))
    )
    (net (code "44") (name "INT2_BERK") (class "Default")
      (node (ref "U4") (pin "55") (pinfunction "PF15_55") (pintype "passive"))
    )
    (net (code "45") (name "INT2_ISM") (class "Default")
      (node (ref "U4") (pin "53") (pinfunction "PF13_53") (pintype "passive"))
    )
    (net (code "46") (name "INT_STT") (class "Default")
      (node (ref "U4") (pin "127") (pinfunction "PG12_127") (pintype "passive"))
    )
    (net (code "47") (name "JTAG_NTRST_GAP") (class "Default")
      (node (ref "J10") (pin "9") (pinfunction "9_9") (pintype "passive"))
      (node (ref "J5") (pin "24") (pinfunction "24_24") (pintype "passive"))
      (node (ref "R57") (pin "2") (pinfunction "2_2") (pintype "passive"))
    )
    (net (code "48") (name "JTAG_TCK_GAP") (class "Default")
      (node (ref "J5") (pin "20") (pinfunction "20_20") (pintype "passive"))
      (node (ref "R53") (pin "2") (pinfunction "2_2") (pintype "passive"))
    )
    (net (code "49") (name "JTAG_TDI_GAP") (class "Default")
      (node (ref "J5") (pin "26") (pinfunction "26_26") (pintype "passive"))
      (node (ref "R55") (pin "2") (pinfunction "2_2") (pintype "passive"))
    )
    (net (code "50") (name "JTAG_TDO_GAP") (class "Default")
      (node (ref "J5") (pin "22") (pinfunction "22_22") (pintype "passive"))
      (node (ref "R54") (pin "2") (pinfunction "2_2") (pintype "passive"))
    )
    (net (code "51") (name "JTAG_TMS_GAP") (class "Default")
      (node (ref "J5") (pin "28") (pinfunction "28_28") (pintype "passive"))
      (node (ref "R52") (pin "2") (pinfunction "2_2") (pintype "passive"))
    )
    (net (code "52") (name "JTCK{slash}SWCLK") (class "Default")
      (node (ref "J6") (pin "4") (pinfunction "4_4") (pintype "passive"))
      (node (ref "U4") (pin "109") (pinfunction "PA14_109") (pintype "passive"))
    )
    (net (code "53") (name "JTDI") (class "Default")
      (node (ref "J6") (pin "8") (pinfunction "8_8") (pintype "passive"))
      (node (ref "U4") (pin "110") (pinfunction "PA15_110") (pintype "passive"))
    )
    (net (code "54") (name "JTDO{slash} SWO") (class "Default")
      (node (ref "J6") (pin "6") (pinfunction "6_6") (pintype "passive"))
      (node (ref "U4") (pin "133") (pinfunction "PB3_133") (pintype "passive"))
    )
    (net (code "55") (name "JTMS{slash}SWDIO") (class "Default")
      (node (ref "J6") (pin "2") (pinfunction "2_2") (pintype "passive"))
      (node (ref "U4") (pin "105") (pinfunction "PA13_105") (pintype "passive"))
    )
    (net (code "56") (name "LED1") (class "Default")
      (node (ref "M1") (pin "1") (pinfunction "G_1") (pintype "passive"))
      (node (ref "U4") (pin "78") (pinfunction "PD9_78") (pintype "passive"))
    )
    (net (code "57") (name "LED2") (class "Default")
      (node (ref "M2") (pin "1") (pinfunction "G_1") (pintype "passive"))
      (node (ref "U4") (pin "79") (pinfunction "PD10_79") (pintype "passive"))
    )
    (net (code "58") (name "LED3") (class "Default")
      (node (ref "M3") (pin "1") (pinfunction "G_1") (pintype "passive"))
      (node (ref "U4") (pin "85") (pinfunction "PD14_85") (pintype "passive"))
    )
    (net (code "59") (name "LED4") (class "Default")
      (node (ref "M4") (pin "1") (pinfunction "G_1") (pintype "passive"))
      (node (ref "U4") (pin "86") (pinfunction "PD15_86") (pintype "passive"))
    )
    (net (code "60") (name "LIS_FS") (class "Default")
      (node (ref "U4") (pin "34") (pinfunction "PA0_34") (pintype "passive"))
    )
    (net (code "61") (name "LIS_PD") (class "Default")
      (node (ref "U4") (pin "29") (pinfunction "PC3_29") (pintype "passive"))
    )
    (net (code "62") (name "LIS_X") (class "Default")
      (node (ref "U4") (pin "26") (pinfunction "PC0_26") (pintype "passive"))
    )
    (net (code "63") (name "LIS_Y") (class "Default")
      (node (ref "U4") (pin "27") (pinfunction "PC1_27") (pintype "passive"))
    )
    (net (code "64") (name "LIS_Z") (class "Default")
      (node (ref "U4") (pin "28") (pinfunction "PC2_28") (pintype "passive"))
    )
    (net (code "65") (name "NB_NET_STATUS") (class "Default")
      (node (ref "U4") (pin "118") (pinfunction "PD4_118") (pintype "passive"))
    )
    (net (code "66") (name "NB_RI") (class "Default")
      (node (ref "U4") (pin "136") (pinfunction "PB6_136") (pintype "passive"))
    )
    (net (code "67") (name "NB_RST") (class "Default")
      (node (ref "U4") (pin "119") (pinfunction "PD5_119") (pintype "passive"))
    )
    (net (code "68") (name "NB_UART_RX") (class "Default")
      (node (ref "U4") (pin "45") (pinfunction "PC5_45") (pintype "passive"))
    )
    (net (code "69") (name "NB_UART_TX") (class "Default")
      (node (ref "U4") (pin "44") (pinfunction "PC4_44") (pintype "passive"))
    )
    (net (code "70") (name "NJTRST") (class "Default")
      (node (ref "J6") (pin "10") (pinfunction "10_10") (pintype "passive"))
      (node (ref "U4") (pin "134") (pinfunction "PB4_134") (pintype "passive"))
    )
    (net (code "71") (name "NRST") (class "Default")
      (node (ref "B2") (pin "A1") (pinfunction "1_A1") (pintype "passive"))
      (node (ref "B2") (pin "C1") (pinfunction "3_C1") (pintype "passive"))
      (node (ref "C51") (pin "1") (pinfunction "1_1") (pintype "passive"))
      (node (ref "J6") (pin "9") (pinfunction "9_9") (pintype "passive"))
      (node (ref "J9") (pin "1") (pinfunction "1_1") (pintype "passive"))
      (node (ref "R14") (pin "1") (pinfunction "1_1") (pintype "passive"))
      (node (ref "U4") (pin "25") (pinfunction "NRST_25") (pintype "passive"))
    )
    (net (code "72") (name "Net-(IC3-B1)") (class "Default")
      (node (ref "IC3") (pin "20") (pinfunction "B1_20") (pintype "passive"))
      (node (ref "R51") (pin "1") (pinfunction "1_1") (pintype "passive"))
    )
    (net (code "73") (name "Net-(IC3-B2)") (class "Default")
      (node (ref "IC3") (pin "18") (pinfunction "B2_18") (pintype "passive"))
      (node (ref "R50") (pin "1") (pinfunction "1_1") (pintype "passive"))
    )
    (net (code "74") (name "Net-(IC3-B3)") (class "Default")
      (node (ref "IC3") (pin "17") (pinfunction "B3_17") (pintype "passive"))
      (node (ref "R44") (pin "1") (pinfunction "1_1") (pintype "passive"))
    )
    (net (code "75") (name "Net-(IC3-B4)") (class "Default")
      (node (ref "IC3") (pin "16") (pinfunction "B4_16") (pintype "passive"))
      (node (ref "R36") (pin "2") (pinfunction "2_2") (pintype "passive"))
    )
    (net (code "76") (name "Net-(IC3-B5)") (class "Default")
      (node (ref "IC3") (pin "15") (pinfunction "B5_15") (pintype "passive"))
      (node (ref "R45") (pin "2") (pinfunction "2_2") (pintype "passive"))
    )
    (net (code "77") (name "Net-(IC3-B6)") (class "Default")
      (node (ref "IC3") (pin "14") (pinfunction "B6_14") (pintype "passive"))
      (node (ref "R47") (pin "2") (pinfunction "2_2") (pintype "passive"))
    )
    (net (code "78") (name "Net-(IC3-B7)") (class "Default")
      (node (ref "IC3") (pin "13") (pinfunction "B7_13") (pintype "passive"))
      (node (ref "R35") (pin "2") (pinfunction "2_2") (pintype "passive"))
    )
    (net (code "79") (name "Net-(IC3-B8)") (class "Default")
      (node (ref "IC3") (pin "12") (pinfunction "B8_12") (pintype "passive"))
      (node (ref "R43") (pin "2") (pinfunction "2_2") (pintype "passive"))
    )
    (net (code "80") (name "Net-(J5-Pad8)") (class "Default")
      (node (ref "J5") (pin "8") (pinfunction "8_8") (pintype "passive"))
      (node (ref "R58") (pin "2") (pinfunction "2_2") (pintype "passive"))
    )
    (net (code "81") (name "Net-(J5-Pad10)") (class "Default")
      (node (ref "J5") (pin "10") (pinfunction "10_10") (pintype "passive"))
      (node (ref "R59") (pin "2") (pinfunction "2_2") (pintype "passive"))
    )
    (net (code "82") (name "Net-(J5-Pad32)") (class "Default")
      (node (ref "J5") (pin "32") (pinfunction "32_32") (pintype "passive"))
      (node (ref "R79") (pin "2") (pinfunction "2_2") (pintype "passive"))
    )
    (net (code "83") (name "Net-(J5-Pad34)") (class "Default")
      (node (ref "J5") (pin "34") (pinfunction "34_34") (pintype "passive"))
      (node (ref "R78") (pin "2") (pinfunction "2_2") (pintype "passive"))
    )
    (net (code "84") (name "Net-(J10-Pad2)") (class "Default")
      (node (ref "J10") (pin "2") (pinfunction "2_2") (pintype "passive"))
      (node (ref "R52") (pin "1") (pinfunction "1_1") (pintype "passive"))
    )
    (net (code "85") (name "Net-(J10-Pad4)") (class "Default")
      (node (ref "J10") (pin "4") (pinfunction "4_4") (pintype "passive"))
      (node (ref "R53") (pin "1") (pinfunction "1_1") (pintype "passive"))
    )
    (net (code "86") (name "Net-(J10-Pad6)") (class "Default")
      (node (ref "J10") (pin "6") (pinfunction "6_6") (pintype "passive"))
      (node (ref "R54") (pin "1") (pinfunction "1_1") (pintype "passive"))
    )
    (net (code "87") (name "Net-(J10-Pad8)") (class "Default")
      (node (ref "J10") (pin "8") (pinfunction "8_8") (pintype "passive"))
      (node (ref "R55") (pin "1") (pinfunction "1_1") (pintype "passive"))
    )
    (net (code "88") (name "Net-(J10-Pad10)") (class "Default")
      (node (ref "J10") (pin "10") (pinfunction "10_10") (pintype "passive"))
      (node (ref "R56") (pin "1") (pinfunction "1_1") (pintype "passive"))
    )
    (net (code "89") (name "Net-(LED1-A)") (class "Default")
      (node (ref "LED1") (pin "2") (pinfunction "A_2") (pintype "passive"))
      (node (ref "R5") (pin "1") (pinfunction "1_1") (pintype "passive"))
    )
    (net (code "90") (name "Net-(LED1-K)") (class "Default")
      (node (ref "LED1") (pin "1") (pinfunction "K_1") (pintype "passive"))
      (node (ref "M1") (pin "3") (pinfunction "D_3") (pintype "passive"))
    )
    (net (code "91") (name "Net-(LED2-A)") (class "Default")
      (node (ref "LED2") (pin "2") (pinfunction "A_2") (pintype "passive"))
      (node (ref "R4") (pin "1") (pinfunction "1_1") (pintype "passive"))
    )
    (net (code "92") (name "Net-(LED2-K)") (class "Default")
      (node (ref "LED2") (pin "1") (pinfunction "K_1") (pintype "passive"))
      (node (ref "M2") (pin "3") (pinfunction "D_3") (pintype "passive"))
    )
    (net (code "93") (name "Net-(LED3-A)") (class "Default")
      (node (ref "LED3") (pin "2") (pinfunction "A_2") (pintype "passive"))
      (node (ref "R6") (pin "1") (pinfunction "1_1") (pintype "passive"))
    )
    (net (code "94") (name "Net-(LED3-K)") (class "Default")
      (node (ref "LED3") (pin "1") (pinfunction "K_1") (pintype "passive"))
      (node (ref "M3") (pin "3") (pinfunction "D_3") (pintype "passive"))
    )
    (net (code "95") (name "Net-(LED4-A)") (class "Default")
      (node (ref "LED4") (pin "2") (pinfunction "A_2") (pintype "passive"))
      (node (ref "R7") (pin "1") (pinfunction "1_1") (pintype "passive"))
    )
    (net (code "96") (name "Net-(LED4-K)") (class "Default")
      (node (ref "LED4") (pin "1") (pinfunction "K_1") (pintype "passive"))
      (node (ref "M4") (pin "3") (pinfunction "D_3") (pintype "passive"))
    )
    (net (code "97") (name "Net-(U4-PC8)") (class "Default")
      (node (ref "R37") (pin "1") (pinfunction "1_1") (pintype "passive"))
      (node (ref "U4") (pin "98") (pinfunction "PC8_98") (pintype "passive"))
    )
    (net (code "98") (name "Net-(U4-PC9)") (class "Default")
      (node (ref "R38") (pin "1") (pinfunction "1_1") (pintype "passive"))
      (node (ref "U4") (pin "99") (pinfunction "PC9_99") (pintype "passive"))
    )
    (net (code "99") (name "Net-(U4-PC10)") (class "Default")
      (node (ref "R39") (pin "1") (pinfunction "1_1") (pintype "passive"))
      (node (ref "U4") (pin "111") (pinfunction "PC10_111") (pintype "passive"))
    )
    (net (code "100") (name "Net-(U4-PC11)") (class "Default")
      (node (ref "R40") (pin "1") (pinfunction "1_1") (pintype "passive"))
      (node (ref "U4") (pin "112") (pinfunction "PC11_112") (pintype "passive"))
    )
    (net (code "101") (name "Net-(U4-PC12)") (class "Default")
      (node (ref "R41") (pin "1") (pinfunction "1_1") (pintype "passive"))
      (node (ref "U4") (pin "113") (pinfunction "PC12_113") (pintype "passive"))
    )
    (net (code "102") (name "Net-(U4-PD2)") (class "Default")
      (node (ref "R42") (pin "1") (pinfunction "1_1") (pintype "passive"))
      (node (ref "U4") (pin "116") (pinfunction "PD2_116") (pintype "passive"))
    )
    (net (code "103") (name "Net-(U4-PH3-BOOT0)") (class "Default")
      (node (ref "R80") (pin "2") (pinfunction "2_2") (pintype "passive"))
      (node (ref "U4") (pin "138") (pinfunction "PH3-BOOT0_138") (pintype "passive"))
    )
    (net (code "104") (name "OCTOSPIM_P1_CLK") (class "Default")
      (node (ref "R45") (pin "1") (pinfunction "1_1") (pintype "passive"))
      (node (ref "U4") (pin "22") (pinfunction "PF10_22") (pintype "passive"))
    )
    (net (code "105") (name "OCTOSPIM_P1_IO0") (class "Default")
      (node (ref "R44") (pin "2") (pinfunction "2_2") (pintype "passive"))
      (node (ref "U4") (pin "20") (pinfunction "PF8_20") (pintype "passive"))
    )
    (net (code "106") (name "OCTOSPIM_P1_IO1") (class "Default")
      (node (ref "R47") (pin "1") (pinfunction "1_1") (pintype "passive"))
      (node (ref "U4") (pin "21") (pinfunction "PF9_21") (pintype "passive"))
    )
    (net (code "107") (name "OCTOSPIM_P1_IO2") (class "Default")
      (node (ref "R51") (pin "2") (pinfunction "2_2") (pintype "passive"))
      (node (ref "U4") (pin "19") (pinfunction "PF7_19") (pintype "passive"))
    )
    (net (code "108") (name "OCTOSPIM_P1_IO3") (class "Default")
      (node (ref "R50") (pin "2") (pinfunction "2_2") (pintype "passive"))
      (node (ref "U4") (pin "18") (pinfunction "PF6_18") (pintype "passive"))
    )
    (net (code "109") (name "OCTOSPIM_P1_NCS") (class "Default")
      (node (ref "R36") (pin "1") (pinfunction "1_1") (pintype "passive"))
      (node (ref "U4") (pin "64") (pinfunction "PE11_64") (pintype "passive"))
    )
    (net (code "110") (name "OCTOSPIM_P2_CLK") (class "Default")
      (node (ref "U4") (pin "14") (pinfunction "PF4_14") (pintype "passive"))
    )
    (net (code "111") (name "OCTOSPIM_P2_IO4") (class "Default")
      (node (ref "U4") (pin "56") (pinfunction "PG0_56") (pintype "passive"))
    )
    (net (code "112") (name "OCTOSPIM_P2_IO5") (class "Default")
      (node (ref "U4") (pin "57") (pinfunction "PG1_57") (pintype "passive"))
    )
    (net (code "113") (name "OCTOSPIM_P2_NCS") (class "Default")
      (node (ref "U4") (pin "117") (pinfunction "PD3_117") (pintype "passive"))
    )
    (net (code "114") (name "OSC32_IN") (class "Default")
      (node (ref "C31") (pin "1") (pinfunction "1_1") (pintype "passive"))
      (node (ref "U4") (pin "8") (pinfunction "PC14-OSC32_IN_8") (pintype "passive"))
      (node (ref "X1") (pin "1") (pinfunction "In_1") (pintype "passive"))
    )
    (net (code "115") (name "OSC32_OUT") (class "Default")
      (node (ref "C32") (pin "1") (pinfunction "1_1") (pintype "passive"))
      (node (ref "U4") (pin "9") (pinfunction "PC15-OSC32_OUT_9") (pintype "passive"))
      (node (ref "X1") (pin "2") (pinfunction "OUT_2") (pintype "passive"))
    )
    (net (code "116") (name "OSC_IN") (class "Default")
      (node (ref "C33") (pin "2") (pinfunction "2_2") (pintype "passive"))
      (node (ref "U4") (pin "23") (pinfunction "PH0-OSC_IN_23") (pintype "passive"))
      (node (ref "X2") (pin "1") (pinfunction "1_1") (pintype "passive"))
    )
    (net (code "117") (name "OSC_OUT") (class "Default")
      (node (ref "C34") (pin "2") (pinfunction "2_2") (pintype "passive"))
      (node (ref "U4") (pin "24") (pinfunction "PH1-OSC_OUT_24") (pintype "passive"))
      (node (ref "X2") (pin "3") (pinfunction "3_3") (pintype "passive"))
    )
    (net (code "118") (name "RAM_PWR_EN") (class "Default")
      (node (ref "J5") (pin "36") (pinfunction "36_36") (pintype "passive"))
      (node (ref "R58") (pin "1") (pinfunction "1_1") (pintype "passive"))
    )
    (net (code "119") (name "RESET_N_GAP") (class "Default")
      (node (ref "J4") (pin "2") (pinfunction "2_2") (pintype "passive"))
      (node (ref "J5") (pin "30") (pinfunction "30_30") (pintype "passive"))
      (node (ref "R56") (pin "2") (pinfunction "2_2") (pintype "passive"))
      (node (ref "R77") (pin "2") (pinfunction "2_2") (pintype "passive"))
    )
    (net (code "120") (name "SAI1_FS_A") (class "Default")
      (node (ref "J8") (pin "13") (pinfunction "13_13") (pintype "passive"))
      (node (ref "U4") (pin "101") (pinfunction "PA9_101") (pintype "passive"))
    )
    (net (code "121") (name "SAI1_FS_B") (class "Default")
      (node (ref "J9") (pin "6") (pinfunction "6_6") (pintype "passive"))
      (node (ref "U4") (pin "60") (pinfunction "PE9_60") (pintype "passive"))
    )
    (net (code "122") (name "SAI1_SCK_A") (class "Default")
      (node (ref "J8") (pin "12") (pinfunction "12_12") (pintype "passive"))
      (node (ref "U4") (pin "100") (pinfunction "PA8_100") (pintype "passive"))
    )
    (net (code "123") (name "SAI1_SCK_B") (class "Default")
      (node (ref "J9") (pin "5") (pinfunction "5_5") (pintype "passive"))
      (node (ref "U4") (pin "59") (pinfunction "PE8_59") (pintype "passive"))
    )
    (net (code "124") (name "SAI1_SD_A") (class "Default")
      (node (ref "J8") (pin "14") (pinfunction "14_14") (pintype "passive"))
      (node (ref "U4") (pin "122") (pinfunction "PD6_122") (pintype "passive"))
    )
    (net (code "125") (name "SAI1_SD_B") (class "Default")
      (node (ref "J9") (pin "7") (pinfunction "7_7") (pintype "passive"))
      (node (ref "U4") (pin "2") (pinfunction "PE3_2") (pintype "passive"))
    )
    (net (code "126") (name "SDMMC1_CLK") (class "Default")
      (node (ref "R41") (pin "2") (pinfunction "2_2") (pintype "passive"))
    )
    (net (code "127") (name "SDMMC1_CMD") (class "Default")
      (node (ref "R42") (pin "2") (pinfunction "2_2") (pintype "passive"))
    )
    (net (code "128") (name "SDMMC1_D0") (class "Default")
      (node (ref "R37") (pin "2") (pinfunction "2_2") (pintype "passive"))
    )
    (net (code "129") (name "SDMMC1_D1") (class "Default")
      (node (ref "R38") (pin "2") (pinfunction "2_2") (pintype "passive"))
    )
    (net (code "130") (name "SDMMC1_D2") (class "Default")
      (node (ref "R39") (pin "2") (pinfunction "2_2") (pintype "passive"))
    )
    (net (code "131") (name "SDMMC1_D3") (class "Default")
      (node (ref "R40") (pin "2") (pinfunction "2_2") (pintype "passive"))
    )
    (net (code "132") (name "SD_BATT_CHG") (class "Default")
      (node (ref "U4") (pin "49") (pinfunction "PF11_49") (pintype "passive"))
    )
    (net (code "133") (name "SPI1_MISO") (class "Default")
      (node (ref "J8") (pin "10") (pinfunction "10_10") (pintype "passive"))
      (node (ref "U4") (pin "67") (pinfunction "PE14_67") (pintype "passive"))
    )
    (net (code "134") (name "SPI1_MOSI") (class "Default")
      (node (ref "J8") (pin "11") (pinfunction "11_11") (pintype "passive"))
      (node (ref "U4") (pin "68") (pinfunction "PE15_68") (pintype "passive"))
    )
    (net (code "135") (name "SPI1_SCK") (class "Default")
      (node (ref "J9") (pin "8") (pinfunction "8_8") (pintype "passive"))
      (node (ref "U4") (pin "41") (pinfunction "PA5_41") (pintype "passive"))
    )
    (net (code "136") (name "SPI3_CLK") (class "Default")
      (node (ref "U4") (pin "124") (pinfunction "PG9_124") (pintype "passive"))
    )
    (net (code "137") (name "SPI3_MISO") (class "Default")
      (node (ref "U4") (pin "125") (pinfunction "PG10_125") (pintype "passive"))
    )
    (net (code "138") (name "SPI3_MOSI") (class "Default")
      (node (ref "U4") (pin "126") (pinfunction "PG11_126") (pintype "passive"))
    )
    (net (code "139") (name "SPI_CS") (class "Default")
      (node (ref "J9") (pin "9") (pinfunction "9_9") (pintype "passive"))
      (node (ref "U4") (pin "40") (pinfunction "PA4_40") (pintype "passive"))
    )
    (net (code "140") (name "UART0_Rx_GAP") (class "Default")
      (node (ref "J4") (pin "4") (pinfunction "4_4") (pintype "passive"))
      (node (ref "J5") (pin "69") (pinfunction "69_69") (pintype "passive"))
    )
    (net (code "141") (name "UART0_Tx_GAP") (class "Default")
      (node (ref "J4") (pin "6") (pinfunction "6_6") (pintype "passive"))
      (node (ref "J5") (pin "71") (pinfunction "71_71") (pintype "passive"))
    )
    (net (code "142") (name "USART2_RX") (class "Default")
      (node (ref "J9") (pin "10") (pinfunction "10_10") (pintype "passive"))
      (node (ref "U4") (pin "37") (pinfunction "PA3_37") (pintype "passive"))
    )
    (net (code "143") (name "USART2_TX") (class "Default")
      (node (ref "J9") (pin "11") (pinfunction "11_11") (pintype "passive"))
      (node (ref "U4") (pin "36") (pinfunction "PA2_36") (pintype "passive"))
    )
    (net (code "144") (name "Usr_button") (class "Default")
      (node (ref "B1") (pin "A1") (pinfunction "1_A1") (pintype "passive"))
      (node (ref "B1") (pin "C1") (pinfunction "3_C1") (pintype "passive"))
      (node (ref "R13") (pin "2") (pinfunction "2_2") (pintype "passive"))
      (node (ref "U4") (pin "114") (pinfunction "PD0_114") (pintype "passive"))
    )
    (net (code "145") (name "V1p8") (class "Default")
      (node (ref "IC3") (pin "2") (pinfunction "VCCA_2") (pintype "passive"))
      (node (ref "J10") (pin "1") (pinfunction "1_1") (pintype "passive"))
      (node (ref "J5") (pin "1") (pinfunction "1_1") (pintype "passive"))
      (node (ref "J5") (pin "3") (pinfunction "3_3") (pintype "passive"))
      (node (ref "J5") (pin "7") (pinfunction "7_7") (pintype "passive"))
      (node (ref "J5") (pin "9") (pinfunction "9_9") (pintype "passive"))
      (node (ref "R57") (pin "1") (pinfunction "1_1") (pintype "passive"))
      (node (ref "R74") (pin "2") (pinfunction "2_2") (pintype "passive"))
      (node (ref "R75") (pin "2") (pinfunction "2_2") (pintype "passive"))
      (node (ref "R77") (pin "1") (pinfunction "1_1") (pintype "passive"))
      (node (ref "R78") (pin "1") (pinfunction "1_1") (pintype "passive"))
      (node (ref "R79") (pin "1") (pinfunction "1_1") (pintype "passive"))
    )
    (net (code "146") (name "WP#_FLASH") (class "Default")
      (node (ref "U4") (pin "87") (pinfunction "PG2_87") (pintype "passive"))
    )
    (net (code "147") (name "mcu_ADC_BATT") (class "Default")
      (node (ref "U4") (pin "48") (pinfunction "PB2_48") (pintype "passive"))
    )
    (net (code "148") (name "unconnected-(J5-Pad5)") (class "Default")
      (node (ref "J5") (pin "5") (pinfunction "5_5") (pintype "passive"))
    )
    (net (code "149") (name "unconnected-(J5-Pad11)") (class "Default")
      (node (ref "J5") (pin "11") (pinfunction "11_11") (pintype "passive"))
    )
    (net (code "150") (name "unconnected-(J5-Pad23)") (class "Default")
      (node (ref "J5") (pin "23") (pinfunction "23_23") (pintype "passive"))
    )
    (net (code "151") (name "unconnected-(J5-Pad25)") (class "Default")
      (node (ref "J5") (pin "25") (pinfunction "25_25") (pintype "passive"))
    )
    (net (code "152") (name "unconnected-(J5-Pad29)") (class "Default")
      (node (ref "J5") (pin "29") (pinfunction "29_29") (pintype "passive"))
    )
    (net (code "153") (name "unconnected-(J5-Pad31)") (class "Default")
      (node (ref "J5") (pin "31") (pinfunction "31_31") (pintype "passive"))
    )
    (net (code "154") (name "unconnected-(J5-Pad35)") (class "Default")
      (node (ref "J5") (pin "35") (pinfunction "35_35") (pintype "passive"))
    )
    (net (code "155") (name "unconnected-(J5-Pad38)") (class "Default")
      (node (ref "J5") (pin "38") (pinfunction "38_38") (pintype "passive"))
    )
    (net (code "156") (name "unconnected-(J5-Pad39)") (class "Default")
      (node (ref "J5") (pin "39") (pinfunction "39_39") (pintype "passive"))
    )
    (net (code "157") (name "unconnected-(J5-Pad40)") (class "Default")
      (node (ref "J5") (pin "40") (pinfunction "40_40") (pintype "passive"))
    )
    (net (code "158") (name "unconnected-(J5-Pad41)") (class "Default")
      (node (ref "J5") (pin "41") (pinfunction "41_41") (pintype "passive"))
    )
    (net (code "159") (name "unconnected-(J5-Pad42)") (class "Default")
      (node (ref "J5") (pin "42") (pinfunction "42_42") (pintype "passive"))
    )
    (net (code "160") (name "unconnected-(J5-Pad43)") (class "Default")
      (node (ref "J5") (pin "43") (pinfunction "43_43") (pintype "passive"))
    )
    (net (code "161") (name "unconnected-(J5-Pad44)") (class "Default")
      (node (ref "J5") (pin "44") (pinfunction "44_44") (pintype "passive"))
    )
    (net (code "162") (name "unconnected-(J5-Pad45)") (class "Default")
      (node (ref "J5") (pin "45") (pinfunction "45_45") (pintype "passive"))
    )
    (net (code "163") (name "unconnected-(J5-Pad46)") (class "Default")
      (node (ref "J5") (pin "46") (pinfunction "46_46") (pintype "passive"))
    )
    (net (code "164") (name "unconnected-(J5-Pad48)") (class "Default")
      (node (ref "J5") (pin "48") (pinfunction "48_48") (pintype "passive"))
    )
    (net (code "165") (name "unconnected-(J5-Pad51)") (class "Default")
      (node (ref "J5") (pin "51") (pinfunction "51_51") (pintype "passive"))
    )
    (net (code "166") (name "unconnected-(J5-Pad52)") (class "Default")
      (node (ref "J5") (pin "52") (pinfunction "52_52") (pintype "passive"))
    )
    (net (code "167") (name "unconnected-(J5-Pad53)") (class "Default")
      (node (ref "J5") (pin "53") (pinfunction "53_53") (pintype "passive"))
    )
    (net (code "168") (name "unconnected-(J5-Pad54)") (class "Default")
      (node (ref "J5") (pin "54") (pinfunction "54_54") (pintype "passive"))
    )
    (net (code "169") (name "unconnected-(J5-Pad68)") (class "Default")
      (node (ref "J5") (pin "68") (pinfunction "68_68") (pintype "passive"))
    )
    (net (code "170") (name "unconnected-(J5-Pad70)") (class "Default")
      (node (ref "J5") (pin "70") (pinfunction "70_70") (pintype "passive"))
    )
    (net (code "171") (name "unconnected-(J5-Pad73)") (class "Default")
      (node (ref "J5") (pin "73") (pinfunction "73_73") (pintype "passive"))
    )
    (net (code "172") (name "unconnected-(J5-Pad74)") (class "Default")
      (node (ref "J5") (pin "74") (pinfunction "74_74") (pintype "passive"))
    )
    (net (code "173") (name "unconnected-(J5-Pad75)") (class "Default")
      (node (ref "J5") (pin "75") (pinfunction "75_75") (pintype "passive"))
    )
    (net (code "174") (name "unconnected-(J6-Pad7)") (class "Default")
      (node (ref "J6") (pin "7") (pinfunction "7_7") (pintype "passive"))
    )
    (net (code "175") (name "unconnected-(J9-Pad12)") (class "Default")
      (node (ref "J9") (pin "12") (pinfunction "12_12") (pintype "passive"))
    )
    (net (code "176") (name "unconnected-(J9-Pad13)") (class "Default")
      (node (ref "J9") (pin "13") (pinfunction "13_13") (pintype "passive"))
    )
    (net (code "177") (name "unconnected-(J9-Pad14)") (class "Default")
      (node (ref "J9") (pin "14") (pinfunction "14_14") (pintype "passive"))
    )
    (net (code "178") (name "unconnected-(J10-Pad7)") (class "Default")
      (node (ref "J10") (pin "7") (pinfunction "7_7") (pintype "passive"))
    )
    (net (code "179") (name "unconnected-(U4-PA1-Pad35)") (class "Default")
      (node (ref "U4") (pin "35") (pinfunction "PA1_35") (pintype "passive"))
    )
    (net (code "180") (name "unconnected-(U4-PA6-Pad42)") (class "Default")
      (node (ref "U4") (pin "42") (pinfunction "PA6_42") (pintype "passive"))
    )
    (net (code "181") (name "unconnected-(U4-PA7-Pad43)") (class "Default")
      (node (ref "U4") (pin "43") (pinfunction "PA7_43") (pintype "passive"))
    )
    (net (code "182") (name "unconnected-(U4-PB5-Pad135)") (class "Default")
      (node (ref "U4") (pin "135") (pinfunction "PB5_135") (pintype "passive"))
    )
    (net (code "183") (name "unconnected-(U4-PB12-Pad73)") (class "Default")
      (node (ref "U4") (pin "73") (pinfunction "PB12_73") (pintype "passive"))
    )
    (net (code "184") (name "unconnected-(U4-PB13-Pad74)") (class "Default")
      (node (ref "U4") (pin "74") (pinfunction "PB13_74") (pintype "passive"))
    )
    (net (code "185") (name "unconnected-(U4-PB14-Pad75)") (class "Default")
      (node (ref "U4") (pin "75") (pinfunction "PB14_75") (pintype "passive"))
    )
    (net (code "186") (name "unconnected-(U4-PB15-Pad76)") (class "Default")
      (node (ref "U4") (pin "76") (pinfunction "PB15_76") (pintype "passive"))
    )
    (net (code "187") (name "unconnected-(U4-PC6-Pad96)") (class "Default")
      (node (ref "U4") (pin "96") (pinfunction "PC6_96") (pintype "passive"))
    )
    (net (code "188") (name "unconnected-(U4-PC7-Pad97)") (class "Default")
      (node (ref "U4") (pin "97") (pinfunction "PC7_97") (pintype "passive"))
    )
    (net (code "189") (name "unconnected-(U4-PC13-Pad7)") (class "Default")
      (node (ref "U4") (pin "7") (pinfunction "PC13_7") (pintype "passive"))
    )
    (net (code "190") (name "unconnected-(U4-PD1-Pad115)") (class "Default")
      (node (ref "U4") (pin "115") (pinfunction "PD1_115") (pintype "passive"))
    )
    (net (code "191") (name "unconnected-(U4-PD7-Pad123)") (class "Default")
      (node (ref "U4") (pin "123") (pinfunction "PD7_123") (pintype "passive"))
    )
    (net (code "192") (name "unconnected-(U4-PD8-Pad77)") (class "Default")
      (node (ref "U4") (pin "77") (pinfunction "PD8_77") (pintype "passive"))
    )
    (net (code "193") (name "unconnected-(U4-PD11-Pad80)") (class "Default")
      (node (ref "U4") (pin "80") (pinfunction "PD11_80") (pintype "passive"))
    )
    (net (code "194") (name "unconnected-(U4-PE0-Pad141)") (class "Default")
      (node (ref "U4") (pin "141") (pinfunction "PE0_141") (pintype "passive"))
    )
    (net (code "195") (name "unconnected-(U4-PE1-Pad142)") (class "Default")
      (node (ref "U4") (pin "142") (pinfunction "PE1_142") (pintype "passive"))
    )
    (net (code "196") (name "unconnected-(U4-PE2-Pad1)") (class "Default")
      (node (ref "U4") (pin "1") (pinfunction "PE2_1") (pintype "passive"))
    )
    (net (code "197") (name "unconnected-(U4-PE4-Pad3)") (class "Default")
      (node (ref "U4") (pin "3") (pinfunction "PE4_3") (pintype "passive"))
    )
    (net (code "198") (name "unconnected-(U4-PE5-Pad4)") (class "Default")
      (node (ref "U4") (pin "4") (pinfunction "PE5_4") (pintype "passive"))
    )
    (net (code "199") (name "unconnected-(U4-PE6-Pad5)") (class "Default")
      (node (ref "U4") (pin "5") (pinfunction "PE6_5") (pintype "passive"))
    )
    (net (code "200") (name "unconnected-(U4-PE7-Pad58)") (class "Default")
      (node (ref "U4") (pin "58") (pinfunction "PE7_58") (pintype "passive"))
    )
    (net (code "201") (name "unconnected-(U4-PE10-Pad63)") (class "Default")
      (node (ref "U4") (pin "63") (pinfunction "PE10_63") (pintype "passive"))
    )
    (net (code "202") (name "unconnected-(U4-PE12-Pad65)") (class "Default")
      (node (ref "U4") (pin "65") (pinfunction "PE12_65") (pintype "passive"))
    )
    (net (code "203") (name "unconnected-(U4-PE13-Pad66)") (class "Default")
      (node (ref "U4") (pin "66") (pinfunction "PE13_66") (pintype "passive"))
    )
    (net (code "204") (name "unconnected-(U4-PF2-Pad12)") (class "Default")
      (node (ref "U4") (pin "12") (pinfunction "PF2_12") (pintype "passive"))
    )
    (net (code "205") (name "unconnected-(U4-PF3-Pad13)") (class "Default")
      (node (ref "U4") (pin "13") (pinfunction "PF3_13") (pintype "passive"))
    )
    (net (code "206") (name "unconnected-(U4-PF5-Pad15)") (class "Default")
      (node (ref "U4") (pin "15") (pinfunction "PF5_15") (pintype "passive"))
    )
    (net (code "207") (name "unconnected-(U4-PG4-Pad89)") (class "Default")
      (node (ref "U4") (pin "89") (pinfunction "PG4_89") (pintype "passive"))
    )
    (net (code "208") (name "unconnected-(U4-PG5-Pad90)") (class "Default")
      (node (ref "U4") (pin "90") (pinfunction "PG5_90") (pintype "passive"))
    )
    (net (code "209") (name "unconnected-(U4-PG6-Pad91)") (class "Default")
      (node (ref "U4") (pin "91") (pinfunction "PG6_91") (pintype "passive"))
    )
  )
)
